# project_vodorezov_switch2.net
KiCad netlist of a schematic drawn in Altium Designer
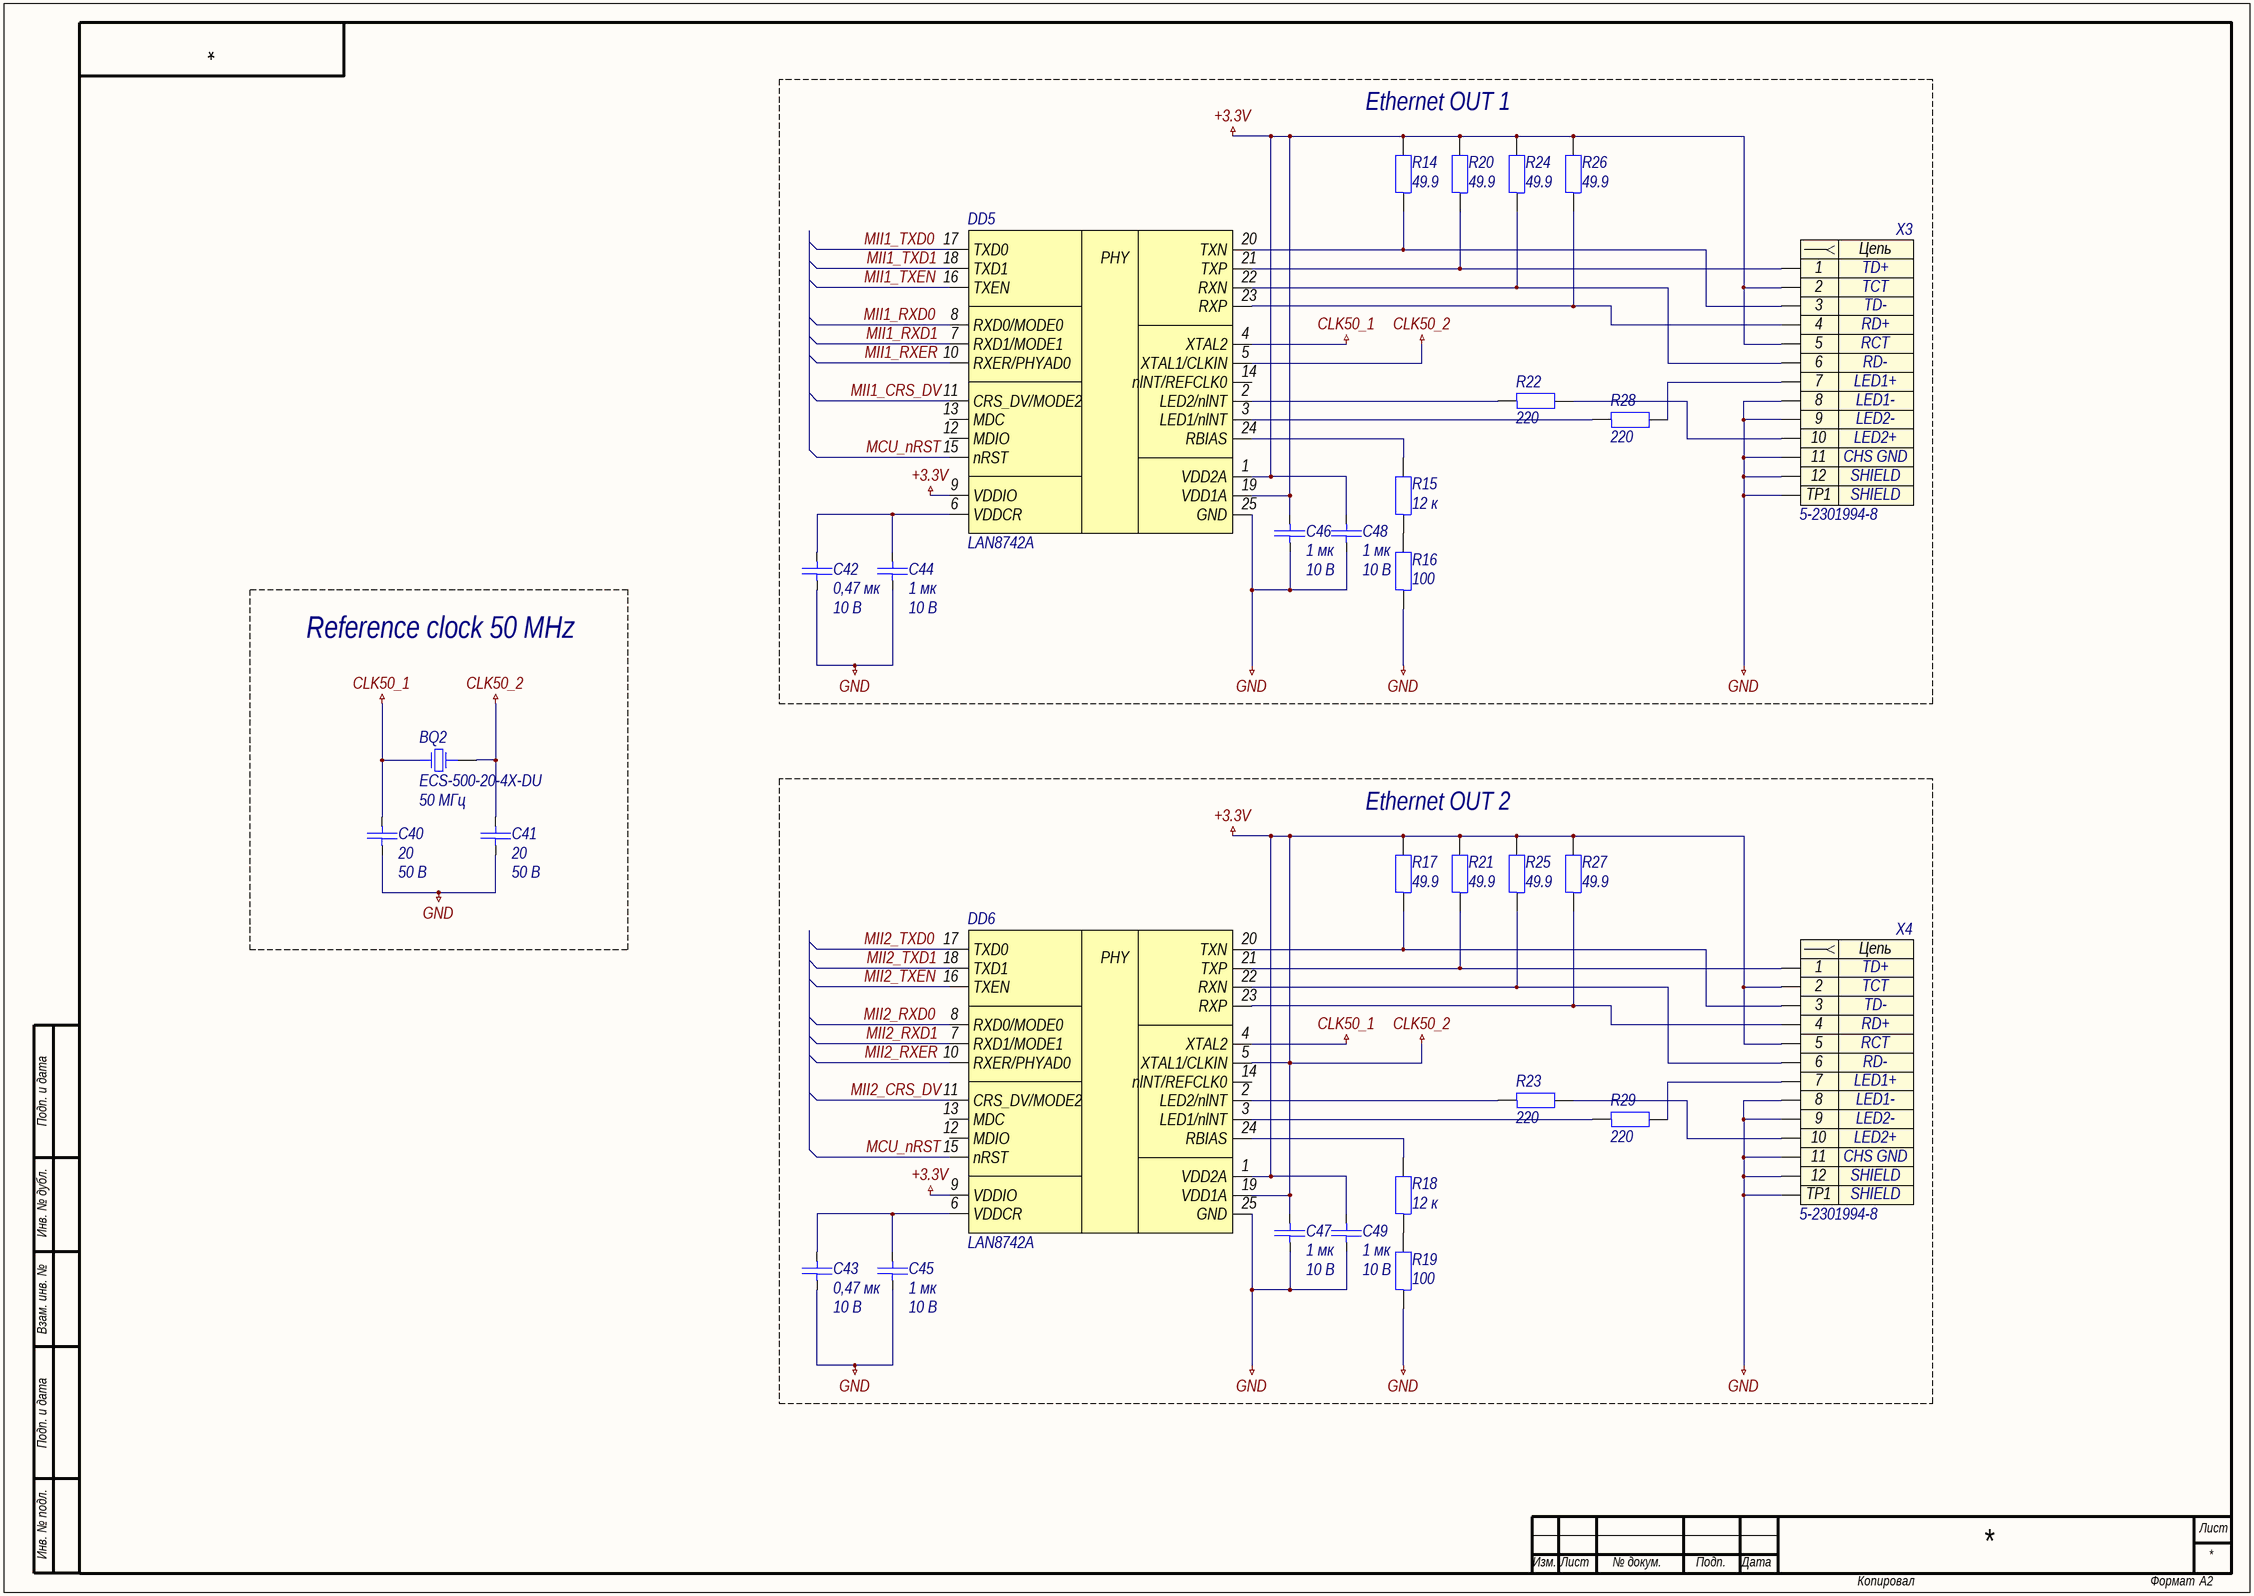
[diagram p0: project_vodorezov_switch2.SchDoc]

(export (version "E")
  (design (tool "Eeschema 10.0.6"))
  (components
    (comp (ref "BQ2")
      (value "ECS-500-20-4X-DU")
      (footprint "HC-49/US")
      (description "=Описание")
      (fields (field (name "ЧАСТОТA") "50 МГц"))
      (libsource (lib "Database_Students") (part "RESONATOR-COMMON"))
    )
    (comp (ref "C40")
      (value "20")
      (footprint "C0402")
      (description "=Описание")
      (fields (field (name "НАПРЯЖЕНИЕ") "50 В"))
      (libsource (lib "Database_Students") (part "CAPACITOR-NONPOLAR"))
    )
    (comp (ref "C41")
      (value "20")
      (footprint "C0402")
      (description "=Описание")
      (fields (field (name "НАПРЯЖЕНИЕ") "50 В"))
      (libsource (lib "Database_Students") (part "CAPACITOR-NONPOLAR"))
    )
    (comp (ref "C42")
      (value "0,47 мк")
      (footprint "C0603")
      (description "=Описание")
      (fields (field (name "НАПРЯЖЕНИЕ") "10 В"))
      (libsource (lib "Database_Students") (part "CAPACITOR-NONPOLAR"))
    )
    (comp (ref "C43")
      (value "0,47 мк")
      (footprint "C0603")
      (description "=Описание")
      (fields (field (name "НАПРЯЖЕНИЕ") "10 В"))
      (libsource (lib "Database_Students") (part "CAPACITOR-NONPOLAR"))
    )
    (comp (ref "C44")
      (value "1 мк")
      (footprint "C0603")
      (description "=Описание")
      (fields (field (name "НАПРЯЖЕНИЕ") "10 В"))
      (libsource (lib "Database_Students") (part "CAPACITOR-NONPOLAR"))
    )
    (comp (ref "C45")
      (value "1 мк")
      (footprint "C0603")
      (description "=Описание")
      (fields (field (name "НАПРЯЖЕНИЕ") "10 В"))
      (libsource (lib "Database_Students") (part "CAPACITOR-NONPOLAR"))
    )
    (comp (ref "C46")
      (value "1 мк")
      (footprint "C0603")
      (description "=Описание")
      (fields (field (name "НАПРЯЖЕНИЕ") "10 В"))
      (libsource (lib "Database_Students") (part "CAPACITOR-NONPOLAR"))
    )
    (comp (ref "C47")
      (value "1 мк")
      (footprint "C0603")
      (description "=Описание")
      (fields (field (name "НАПРЯЖЕНИЕ") "10 В"))
      (libsource (lib "Database_Students") (part "CAPACITOR-NONPOLAR"))
    )
    (comp (ref "C48")
      (value "1 мк")
      (footprint "C0603")
      (description "=Описание")
      (fields (field (name "НАПРЯЖЕНИЕ") "10 В"))
      (libsource (lib "Database_Students") (part "CAPACITOR-NONPOLAR"))
    )
    (comp (ref "C49")
      (value "1 мк")
      (footprint "C0603")
      (description "=Описание")
      (fields (field (name "НАПРЯЖЕНИЕ") "10 В"))
      (libsource (lib "Database_Students") (part "CAPACITOR-NONPOLAR"))
    )
    (comp (ref "DD5")
      (value "LAN8742A")
      (footprint "QFN-24-P50-400X400X80-L40X25-T270X270")
      (description "=Описание")
      (libsource (lib "Database_Students") (part "LAN8742A"))
    )
    (comp (ref "DD6")
      (value "LAN8742A")
      (footprint "QFN-24-P50-400X400X80-L40X25-T270X270")
      (description "=Описание")
      (libsource (lib "Database_Students") (part "LAN8742A"))
    )
    (comp (ref "R14")
      (value "49.9")
      (footprint "R0603")
      (description "=Описание")
      (libsource (lib "Database_Students") (part "RESISTOR-COMMON"))
    )
    (comp (ref "R15")
      (value "12 к")
      (footprint "R0603")
      (description "=Описание")
      (libsource (lib "Database_Students") (part "RESISTOR-COMMON"))
    )
    (comp (ref "R16")
      (value "100")
      (footprint "R0603")
      (description "=Описание")
      (libsource (lib "Database_Students") (part "RESISTOR-COMMON"))
    )
    (comp (ref "R17")
      (value "49.9")
      (footprint "R0603")
      (description "=Описание")
      (libsource (lib "Database_Students") (part "RESISTOR-COMMON"))
    )
    (comp (ref "R18")
      (value "12 к")
      (footprint "R0603")
      (description "=Описание")
      (libsource (lib "Database_Students") (part "RESISTOR-COMMON"))
    )
    (comp (ref "R19")
      (value "100")
      (footprint "R0603")
      (description "=Описание")
      (libsource (lib "Database_Students") (part "RESISTOR-COMMON"))
    )
    (comp (ref "R20")
      (value "49.9")
      (footprint "R0603")
      (description "=Описание")
      (libsource (lib "Database_Students") (part "RESISTOR-COMMON"))
    )
    (comp (ref "R21")
      (value "49.9")
      (footprint "R0603")
      (description "=Описание")
      (libsource (lib "Database_Students") (part "RESISTOR-COMMON"))
    )
    (comp (ref "R22")
      (value "220")
      (footprint "R0603")
      (description "=Описание")
      (libsource (lib "Database_Students") (part "RESISTOR-COMMON"))
    )
    (comp (ref "R23")
      (value "220")
      (footprint "R0603")
      (description "=Описание")
      (libsource (lib "Database_Students") (part "RESISTOR-COMMON"))
    )
    (comp (ref "R24")
      (value "49.9")
      (footprint "R0603")
      (description "=Описание")
      (libsource (lib "Database_Students") (part "RESISTOR-COMMON"))
    )
    (comp (ref "R25")
      (value "49.9")
      (footprint "R0603")
      (description "=Описание")
      (libsource (lib "Database_Students") (part "RESISTOR-COMMON"))
    )
    (comp (ref "R26")
      (value "49.9")
      (footprint "R0603")
      (description "=Описание")
      (libsource (lib "Database_Students") (part "RESISTOR-COMMON"))
    )
    (comp (ref "R27")
      (value "49.9")
      (footprint "R0603")
      (description "=Описание")
      (libsource (lib "Database_Students") (part "RESISTOR-COMMON"))
    )
    (comp (ref "R28")
      (value "220")
      (footprint "R0603")
      (description "=Описание")
      (libsource (lib "Database_Students") (part "RESISTOR-COMMON"))
    )
    (comp (ref "R29")
      (value "220")
      (footprint "R0603")
      (description "=Описание")
      (libsource (lib "Database_Students") (part "RESISTOR-COMMON"))
    )
    (comp (ref "X3")
      (value "5-2301994-8")
      (footprint "5-2301994-8")
      (description "=Описание")
      (libsource (lib "Database_Students") (part "HEADER-12-TP1-SCT"))
    )
    (comp (ref "X4")
      (value "5-2301994-8")
      (footprint "5-2301994-8")
      (description "=Описание")
      (libsource (lib "Database_Students") (part "HEADER-12-TP1-SCT"))
    )
  )
  (nets
    (net (code "1") (name "+3.3V") (class "Default")
      (node (ref "BQ2") (pin "2") (pinfunction "2_2") (pintype "passive"))
      (node (ref "C41") (pin "1") (pinfunction "1_1") (pintype "passive"))
      (node (ref "C46") (pin "1") (pinfunction "1_1") (pintype "passive"))
      (node (ref "C47") (pin "1") (pinfunction "1_1") (pintype "passive"))
      (node (ref "C48") (pin "1") (pinfunction "1_1") (pintype "passive"))
      (node (ref "C49") (pin "1") (pinfunction "1_1") (pintype "passive"))
      (node (ref "DD5") (pin "1") (pinfunction "VDD2A_1") (pintype "passive"))
      (node (ref "DD5") (pin "19") (pinfunction "VDD1A_19") (pintype "passive"))
      (node (ref "DD5") (pin "5") (pinfunction "XTAL1/CLKIN_5") (pintype "passive"))
      (node (ref "DD5") (pin "9") (pinfunction "VDDIO_9") (pintype "passive"))
      (node (ref "DD6") (pin "1") (pinfunction "VDD2A_1") (pintype "passive"))
      (node (ref "DD6") (pin "19") (pinfunction "VDD1A_19") (pintype "passive"))
      (node (ref "DD6") (pin "5") (pinfunction "XTAL1/CLKIN_5") (pintype "passive"))
      (node (ref "DD6") (pin "9") (pinfunction "VDDIO_9") (pintype "passive"))
      (node (ref "R14") (pin "2") (pinfunction "2_2") (pintype "passive"))
      (node (ref "R17") (pin "2") (pinfunction "2_2") (pintype "passive"))
      (node (ref "R20") (pin "2") (pinfunction "2_2") (pintype "passive"))
      (node (ref "R21") (pin "2") (pinfunction "2_2") (pintype "passive"))
      (node (ref "R24") (pin "2") (pinfunction "2_2") (pintype "passive"))
      (node (ref "R25") (pin "2") (pinfunction "2_2") (pintype "passive"))
      (node (ref "R26") (pin "2") (pinfunction "2_2") (pintype "passive"))
      (node (ref "R27") (pin "2") (pinfunction "2_2") (pintype "passive"))
      (node (ref "X3") (pin "2") (pinfunction "2_2") (pintype "passive"))
      (node (ref "X3") (pin "5") (pinfunction "5_5") (pintype "passive"))
      (node (ref "X4") (pin "2") (pinfunction "2_2") (pintype "passive"))
      (node (ref "X4") (pin "5") (pinfunction "5_5") (pintype "passive"))
    )
    (net (code "2") (name "/MCU_nRST") (class "Default")
      (node (ref "DD5") (pin "15") (pinfunction "nRST_15") (pintype "passive"))
      (node (ref "DD6") (pin "15") (pinfunction "nRST_15") (pintype "passive"))
    )
    (net (code "3") (name "/MII1_CRS_DV") (class "Default")
      (node (ref "DD5") (pin "11") (pinfunction "CRS_DV/MODE2_11") (pintype "passive"))
    )
    (net (code "4") (name "/MII1_RXD0") (class "Default")
      (node (ref "DD5") (pin "8") (pinfunction "RXD0/MODE0_8") (pintype "passive"))
    )
    (net (code "5") (name "/MII1_RXD1") (class "Default")
      (node (ref "DD5") (pin "7") (pinfunction "RXD1/MODE1_7") (pintype "passive"))
    )
    (net (code "6") (name "/MII1_RXER") (class "Default")
      (node (ref "DD5") (pin "10") (pinfunction "RXER/PHYAD0_10") (pintype "passive"))
    )
    (net (code "7") (name "/MII1_TXD0") (class "Default")
      (node (ref "DD5") (pin "17") (pinfunction "TXD0_17") (pintype "passive"))
    )
    (net (code "8") (name "/MII1_TXD1") (class "Default")
      (node (ref "DD5") (pin "18") (pinfunction "TXD1_18") (pintype "passive"))
    )
    (net (code "9") (name "/MII1_TXEN") (class "Default")
      (node (ref "DD5") (pin "16") (pinfunction "TXEN_16") (pintype "passive"))
    )
    (net (code "10") (name "/MII2_CRS_DV") (class "Default")
      (node (ref "DD6") (pin "11") (pinfunction "CRS_DV/MODE2_11") (pintype "passive"))
    )
    (net (code "11") (name "/MII2_RXD0") (class "Default")
      (node (ref "DD6") (pin "8") (pinfunction "RXD0/MODE0_8") (pintype "passive"))
    )
    (net (code "12") (name "/MII2_RXD1") (class "Default")
      (node (ref "DD6") (pin "7") (pinfunction "RXD1/MODE1_7") (pintype "passive"))
    )
    (net (code "13") (name "/MII2_RXER") (class "Default")
      (node (ref "DD6") (pin "10") (pinfunction "RXER/PHYAD0_10") (pintype "passive"))
    )
    (net (code "14") (name "/MII2_TXD0") (class "Default")
      (node (ref "DD6") (pin "17") (pinfunction "TXD0_17") (pintype "passive"))
    )
    (net (code "15") (name "/MII2_TXD1") (class "Default")
      (node (ref "DD6") (pin "18") (pinfunction "TXD1_18") (pintype "passive"))
    )
    (net (code "16") (name "/MII2_TXEN") (class "Default")
      (node (ref "DD6") (pin "16") (pinfunction "TXEN_16") (pintype "passive"))
    )
    (net (code "17") (name "CLK50_1") (class "Default")
      (node (ref "BQ2") (pin "1") (pinfunction "1_1") (pintype "passive"))
      (node (ref "C40") (pin "1") (pinfunction "1_1") (pintype "passive"))
      (node (ref "DD5") (pin "4") (pinfunction "XTAL2_4") (pintype "passive"))
      (node (ref "DD6") (pin "4") (pinfunction "XTAL2_4") (pintype "passive"))
    )
    (net (code "18") (name "GND") (class "Default")
      (node (ref "C40") (pin "2") (pinfunction "2_2") (pintype "passive"))
      (node (ref "C41") (pin "2") (pinfunction "2_2") (pintype "passive"))
      (node (ref "C42") (pin "2") (pinfunction "2_2") (pintype "passive"))
      (node (ref "C43") (pin "2") (pinfunction "2_2") (pintype "passive"))
      (node (ref "C44") (pin "2") (pinfunction "2_2") (pintype "passive"))
      (node (ref "C45") (pin "2") (pinfunction "2_2") (pintype "passive"))
      (node (ref "C46") (pin "2") (pinfunction "2_2") (pintype "passive"))
      (node (ref "C47") (pin "2") (pinfunction "2_2") (pintype "passive"))
      (node (ref "C48") (pin "2") (pinfunction "2_2") (pintype "passive"))
      (node (ref "C49") (pin "2") (pinfunction "2_2") (pintype "passive"))
      (node (ref "DD5") (pin "25") (pinfunction "GND_25") (pintype "passive"))
      (node (ref "DD6") (pin "25") (pinfunction "GND_25") (pintype "passive"))
      (node (ref "R16") (pin "1") (pinfunction "1_1") (pintype "passive"))
      (node (ref "R19") (pin "1") (pinfunction "1_1") (pintype "passive"))
      (node (ref "X3") (pin "11") (pinfunction "11_11") (pintype "passive"))
      (node (ref "X3") (pin "12") (pinfunction "12_12") (pintype "passive"))
      (node (ref "X3") (pin "8") (pinfunction "8_8") (pintype "passive"))
      (node (ref "X3") (pin "9") (pinfunction "9_9") (pintype "passive"))
      (node (ref "X3") (pin "TP1") (pinfunction "TP1_TP1") (pintype "passive"))
      (node (ref "X4") (pin "11") (pinfunction "11_11") (pintype "passive"))
      (node (ref "X4") (pin "12") (pinfunction "12_12") (pintype "passive"))
      (node (ref "X4") (pin "8") (pinfunction "8_8") (pintype "passive"))
      (node (ref "X4") (pin "9") (pinfunction "9_9") (pintype "passive"))
      (node (ref "X4") (pin "TP1") (pinfunction "TP1_TP1") (pintype "passive"))
    )
    (net (code "19") (name "Net-(DD5-LED1{slash}nlNT)") (class "Default")
      (node (ref "DD5") (pin "3") (pinfunction "LED1/nlNT_3") (pintype "passive"))
      (node (ref "R28") (pin "1") (pinfunction "1_1") (pintype "passive"))
    )
    (net (code "20") (name "Net-(DD5-LED2{slash}nlNT)") (class "Default")
      (node (ref "DD5") (pin "2") (pinfunction "LED2/nlNT_2") (pintype "passive"))
      (node (ref "R22") (pin "1") (pinfunction "1_1") (pintype "passive"))
    )
    (net (code "21") (name "Net-(DD5-RBIAS)") (class "Default")
      (node (ref "DD5") (pin "24") (pinfunction "RBIAS_24") (pintype "passive"))
      (node (ref "R15") (pin "2") (pinfunction "2_2") (pintype "passive"))
    )
    (net (code "22") (name "Net-(DD5-RXN)") (class "Default")
      (node (ref "DD5") (pin "22") (pinfunction "RXN_22") (pintype "passive"))
      (node (ref "R24") (pin "1") (pinfunction "1_1") (pintype "passive"))
      (node (ref "X3") (pin "6") (pinfunction "6_6") (pintype "passive"))
    )
    (net (code "23") (name "Net-(DD5-RXP)") (class "Default")
      (node (ref "DD5") (pin "23") (pinfunction "RXP_23") (pintype "passive"))
      (node (ref "R26") (pin "1") (pinfunction "1_1") (pintype "passive"))
      (node (ref "X3") (pin "4") (pinfunction "4_4") (pintype "passive"))
    )
    (net (code "24") (name "Net-(DD5-TXN)") (class "Default")
      (node (ref "DD5") (pin "20") (pinfunction "TXN_20") (pintype "passive"))
      (node (ref "R14") (pin "1") (pinfunction "1_1") (pintype "passive"))
      (node (ref "X3") (pin "3") (pinfunction "3_3") (pintype "passive"))
    )
    (net (code "25") (name "Net-(DD5-TXP)") (class "Default")
      (node (ref "DD5") (pin "21") (pinfunction "TXP_21") (pintype "passive"))
      (node (ref "R20") (pin "1") (pinfunction "1_1") (pintype "passive"))
      (node (ref "X3") (pin "1") (pinfunction "1_1") (pintype "passive"))
    )
    (net (code "26") (name "Net-(DD5-VDDCR)") (class "Default")
      (node (ref "C42") (pin "1") (pinfunction "1_1") (pintype "passive"))
      (node (ref "C44") (pin "1") (pinfunction "1_1") (pintype "passive"))
      (node (ref "DD5") (pin "6") (pinfunction "VDDCR_6") (pintype "passive"))
    )
    (net (code "27") (name "Net-(DD6-LED1{slash}nlNT)") (class "Default")
      (node (ref "DD6") (pin "3") (pinfunction "LED1/nlNT_3") (pintype "passive"))
      (node (ref "R29") (pin "1") (pinfunction "1_1") (pintype "passive"))
    )
    (net (code "28") (name "Net-(DD6-LED2{slash}nlNT)") (class "Default")
      (node (ref "DD6") (pin "2") (pinfunction "LED2/nlNT_2") (pintype "passive"))
      (node (ref "R23") (pin "1") (pinfunction "1_1") (pintype "passive"))
    )
    (net (code "29") (name "Net-(DD6-RBIAS)") (class "Default")
      (node (ref "DD6") (pin "24") (pinfunction "RBIAS_24") (pintype "passive"))
      (node (ref "R18") (pin "2") (pinfunction "2_2") (pintype "passive"))
    )
    (net (code "30") (name "Net-(DD6-RXN)") (class "Default")
      (node (ref "DD6") (pin "22") (pinfunction "RXN_22") (pintype "passive"))
      (node (ref "R25") (pin "1") (pinfunction "1_1") (pintype "passive"))
      (node (ref "X4") (pin "6") (pinfunction "6_6") (pintype "passive"))
    )
    (net (code "31") (name "Net-(DD6-RXP)") (class "Default")
      (node (ref "DD6") (pin "23") (pinfunction "RXP_23") (pintype "passive"))
      (node (ref "R27") (pin "1") (pinfunction "1_1") (pintype "passive"))
      (node (ref "X4") (pin "4") (pinfunction "4_4") (pintype "passive"))
    )
    (net (code "32") (name "Net-(DD6-TXN)") (class "Default")
      (node (ref "DD6") (pin "20") (pinfunction "TXN_20") (pintype "passive"))
      (node (ref "R17") (pin "1") (pinfunction "1_1") (pintype "passive"))
      (node (ref "X4") (pin "3") (pinfunction "3_3") (pintype "passive"))
    )
    (net (code "33") (name "Net-(DD6-TXP)") (class "Default")
      (node (ref "DD6") (pin "21") (pinfunction "TXP_21") (pintype "passive"))
      (node (ref "R21") (pin "1") (pinfunction "1_1") (pintype "passive"))
      (node (ref "X4") (pin "1") (pinfunction "1_1") (pintype "passive"))
    )
    (net (code "34") (name "Net-(DD6-VDDCR)") (class "Default")
      (node (ref "C43") (pin "1") (pinfunction "1_1") (pintype "passive"))
      (node (ref "C45") (pin "1") (pinfunction "1_1") (pintype "passive"))
      (node (ref "DD6") (pin "6") (pinfunction "VDDCR_6") (pintype "passive"))
    )
    (net (code "35") (name "Net-(R15-Pad1)") (class "Default")
      (node (ref "R15") (pin "1") (pinfunction "1_1") (pintype "passive"))
      (node (ref "R16") (pin "2") (pinfunction "2_2") (pintype "passive"))
    )
    (net (code "36") (name "Net-(R18-Pad1)") (class "Default")
      (node (ref "R18") (pin "1") (pinfunction "1_1") (pintype "passive"))
      (node (ref "R19") (pin "2") (pinfunction "2_2") (pintype "passive"))
    )
    (net (code "37") (name "Net-(R22-Pad2)") (class "Default")
      (node (ref "R22") (pin "2") (pinfunction "2_2") (pintype "passive"))
      (node (ref "X3") (pin "10") (pinfunction "10_10") (pintype "passive"))
    )
    (net (code "38") (name "Net-(R23-Pad2)") (class "Default")
      (node (ref "R23") (pin "2") (pinfunction "2_2") (pintype "passive"))
      (node (ref "X4") (pin "10") (pinfunction "10_10") (pintype "passive"))
    )
    (net (code "39") (name "Net-(R28-Pad2)") (class "Default")
      (node (ref "R28") (pin "2") (pinfunction "2_2") (pintype "passive"))
      (node (ref "X3") (pin "7") (pinfunction "7_7") (pintype "passive"))
    )
    (net (code "40") (name "Net-(R29-Pad2)") (class "Default")
      (node (ref "R29") (pin "2") (pinfunction "2_2") (pintype "passive"))
      (node (ref "X4") (pin "7") (pinfunction "7_7") (pintype "passive"))
    )
    (net (code "41") (name "unconnected-(DD5-MDC-Pad13)") (class "Default")
      (node (ref "DD5") (pin "13") (pinfunction "MDC_13") (pintype "passive"))
    )
    (net (code "42") (name "unconnected-(DD5-MDIO-Pad12)") (class "Default")
      (node (ref "DD5") (pin "12") (pinfunction "MDIO_12") (pintype "passive"))
    )
    (net (code "43") (name "unconnected-(DD5-nlNT{slash}REFCLK0-Pad14)") (class "Default")
      (node (ref "DD5") (pin "14") (pinfunction "nlNT/REFCLK0_14") (pintype "passive"))
    )
    (net (code "44") (name "unconnected-(DD6-MDC-Pad13)") (class "Default")
      (node (ref "DD6") (pin "13") (pinfunction "MDC_13") (pintype "passive"))
    )
    (net (code "45") (name "unconnected-(DD6-MDIO-Pad12)") (class "Default")
      (node (ref "DD6") (pin "12") (pinfunction "MDIO_12") (pintype "passive"))
    )
    (net (code "46") (name "unconnected-(DD6-nlNT{slash}REFCLK0-Pad14)") (class "Default")
      (node (ref "DD6") (pin "14") (pinfunction "nlNT/REFCLK0_14") (pintype "passive"))
    )
  )
)
